# Low_Distortion_Oscillator_DCDC.net
KiCad netlist of a schematic drawn in Altium Designer
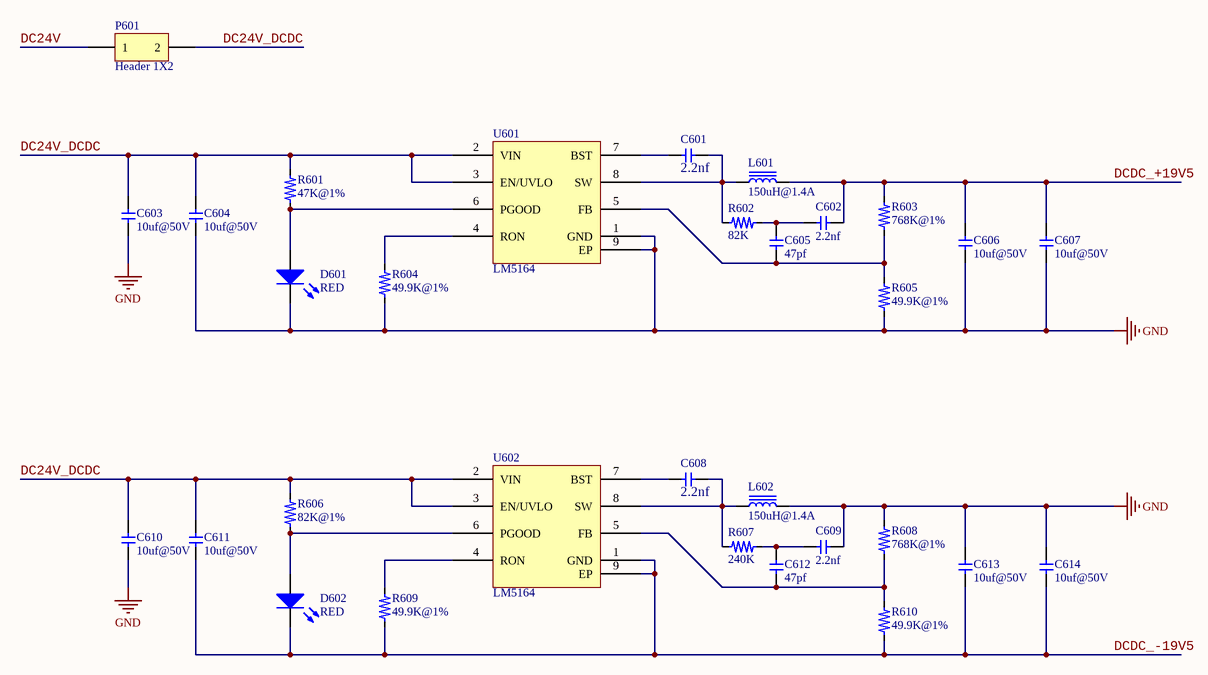
[diagram p0: Low Distortion Oscillator.DCDC.SchDoc]

(export (version "E")
  (design (tool "Eeschema 10.0.6"))
  (components
    (comp (ref "C601")
      (value "2.2nf")
      (footprint "C0603")
      (fields (field (name "Comment") "Cap"))
      (libsource (lib "carrot_lib") (part "Cap"))
    )
    (comp (ref "C602")
      (value "2.2nf")
      (footprint "C0603")
      (fields (field (name "Comment") "Cap"))
      (libsource (lib "carrot_lib") (part "Cap"))
    )
    (comp (ref "C603")
      (value "10uf@50V")
      (footprint "C1206")
      (fields (field (name "Comment") "Cap"))
      (libsource (lib "carrot_lib") (part "Cap"))
    )
    (comp (ref "C604")
      (value "10uf@50V")
      (footprint "C1206")
      (fields (field (name "Comment") "Cap"))
      (libsource (lib "carrot_lib") (part "Cap"))
    )
    (comp (ref "C605")
      (value "47pf")
      (footprint "C0603")
      (fields (field (name "Comment") "Cap"))
      (libsource (lib "carrot_lib") (part "Cap"))
    )
    (comp (ref "C606")
      (value "10uf@50V")
      (footprint "C1206")
      (fields (field (name "Comment") "Cap"))
      (libsource (lib "carrot_lib") (part "Cap"))
    )
    (comp (ref "C607")
      (value "10uf@50V")
      (footprint "C1206")
      (fields (field (name "Comment") "Cap"))
      (libsource (lib "carrot_lib") (part "Cap"))
    )
    (comp (ref "C608")
      (value "2.2nf")
      (footprint "C0603")
      (fields (field (name "Comment") "Cap"))
      (libsource (lib "carrot_lib") (part "Cap"))
    )
    (comp (ref "C609")
      (value "2.2nf")
      (footprint "C0603")
      (fields (field (name "Comment") "Cap"))
      (libsource (lib "carrot_lib") (part "Cap"))
    )
    (comp (ref "C610")
      (value "10uf@50V")
      (footprint "C1206")
      (fields (field (name "Comment") "Cap"))
      (libsource (lib "carrot_lib") (part "Cap"))
    )
    (comp (ref "C611")
      (value "10uf@50V")
      (footprint "C1206")
      (fields (field (name "Comment") "Cap"))
      (libsource (lib "carrot_lib") (part "Cap"))
    )
    (comp (ref "C612")
      (value "47pf")
      (footprint "C0603")
      (fields (field (name "Comment") "Cap"))
      (libsource (lib "carrot_lib") (part "Cap"))
    )
    (comp (ref "C613")
      (value "10uf@50V")
      (footprint "C1206")
      (fields (field (name "Comment") "Cap"))
      (libsource (lib "carrot_lib") (part "Cap"))
    )
    (comp (ref "C614")
      (value "10uf@50V")
      (footprint "C1206")
      (fields (field (name "Comment") "Cap"))
      (libsource (lib "carrot_lib") (part "Cap"))
    )
    (comp (ref "D601")
      (value "RED")
      (footprint "LED0603")
      (fields (field (name "Comment") "LED"))
      (libsource (lib "carrot_lib") (part "LED"))
    )
    (comp (ref "D602")
      (value "RED")
      (footprint "LED0603")
      (fields (field (name "Comment") "LED"))
      (libsource (lib "carrot_lib") (part "LED"))
    )
    (comp (ref "L601")
      (value "150uH@1.4A")
      (footprint "L12127")
      (description "Magnetic-Core Inductor")
      (fields (field (name "Comment") "Inductor Iron"))
      (libsource (lib "carrot_lib") (part "Inductor Iron"))
    )
    (comp (ref "L602")
      (value "150uH@1.4A")
      (footprint "L12127")
      (description "Magnetic-Core Inductor")
      (fields (field (name "Comment") "Inductor Iron"))
      (libsource (lib "carrot_lib") (part "Inductor Iron"))
    )
    (comp (ref "P601")
      (value "Header 1X2")
      (footprint "HDR2X1")
      (description "Header, 1-Pin, Dual row")
      (libsource (lib "carrot_lib") (part "Header 1X2"))
    )
    (comp (ref "R601")
      (value "47K@1%")
      (footprint "R0603")
      (description "电阻")
      (fields (field (name "Comment") "Res"))
      (libsource (lib "carrot_lib") (part "Res"))
    )
    (comp (ref "R602")
      (value "82K")
      (footprint "R0603")
      (description "电阻")
      (fields (field (name "Comment") "Res"))
      (libsource (lib "carrot_lib") (part "Res"))
    )
    (comp (ref "R603")
      (value "768K@1%")
      (footprint "R0603")
      (description "电阻")
      (fields (field (name "Comment") "Res"))
      (libsource (lib "carrot_lib") (part "Res"))
    )
    (comp (ref "R604")
      (value "49.9K@1%")
      (footprint "R0603")
      (description "电阻")
      (fields (field (name "Comment") "Res"))
      (libsource (lib "carrot_lib") (part "Res"))
    )
    (comp (ref "R605")
      (value "49.9K@1%")
      (footprint "R0603")
      (description "电阻")
      (fields (field (name "Comment") "Res"))
      (libsource (lib "carrot_lib") (part "Res"))
    )
    (comp (ref "R606")
      (value "82K@1%")
      (footprint "R0603")
      (description "电阻")
      (fields (field (name "Comment") "Res"))
      (libsource (lib "carrot_lib") (part "Res"))
    )
    (comp (ref "R607")
      (value "240K")
      (footprint "R0603")
      (description "电阻")
      (fields (field (name "Comment") "Res"))
      (libsource (lib "carrot_lib") (part "Res"))
    )
    (comp (ref "R608")
      (value "768K@1%")
      (footprint "R0603")
      (description "电阻")
      (fields (field (name "Comment") "Res"))
      (libsource (lib "carrot_lib") (part "Res"))
    )
    (comp (ref "R609")
      (value "49.9K@1%")
      (footprint "R0603")
      (description "电阻")
      (fields (field (name "Comment") "Res"))
      (libsource (lib "carrot_lib") (part "Res"))
    )
    (comp (ref "R610")
      (value "49.9K@1%")
      (footprint "R0603")
      (description "电阻")
      (fields (field (name "Comment") "Res"))
      (libsource (lib "carrot_lib") (part "Res"))
    )
    (comp (ref "U601")
      (value "LM5164")
      (footprint "LM5164-SOIC8")
      (description "LM5164 100-V Input, 1-A synchronous buck DC/DC converter with ultra-low IQ")
      (libsource (lib "carrot_lib") (part "LM5164"))
    )
    (comp (ref "U602")
      (value "LM5164")
      (footprint "LM5164-SOIC8")
      (description "LM5164 100-V Input, 1-A synchronous buck DC/DC converter with ultra-low IQ")
      (libsource (lib "carrot_lib") (part "LM5164"))
    )
  )
  (nets
    (net (code "1") (name "/DC24V") (class "Default")
      (node (ref "P601") (pin "1") (pinfunction "1_1") (pintype "passive"))
    )
    (net (code "2") (name "/DC24V_DCDC") (class "Default")
      (node (ref "C603") (pin "2") (pinfunction "2_2") (pintype "passive"))
      (node (ref "C604") (pin "2") (pinfunction "2_2") (pintype "passive"))
      (node (ref "C610") (pin "2") (pinfunction "2_2") (pintype "passive"))
      (node (ref "C611") (pin "2") (pinfunction "2_2") (pintype "passive"))
      (node (ref "P601") (pin "2") (pinfunction "2_2") (pintype "passive"))
      (node (ref "R601") (pin "2") (pinfunction "2_2") (pintype "passive"))
      (node (ref "R606") (pin "2") (pinfunction "2_2") (pintype "passive"))
      (node (ref "U601") (pin "2") (pinfunction "VIN_2") (pintype "passive"))
      (node (ref "U601") (pin "3") (pinfunction "EN/UVLO_3") (pintype "passive"))
      (node (ref "U602") (pin "2") (pinfunction "VIN_2") (pintype "passive"))
      (node (ref "U602") (pin "3") (pinfunction "EN/UVLO_3") (pintype "passive"))
    )
    (net (code "3") (name "/DCDC_+19V5") (class "Default")
      (node (ref "C602") (pin "2") (pinfunction "2_2") (pintype "passive"))
      (node (ref "C606") (pin "2") (pinfunction "2_2") (pintype "passive"))
      (node (ref "C607") (pin "2") (pinfunction "2_2") (pintype "passive"))
      (node (ref "L601") (pin "2") (pinfunction "2_2") (pintype "passive"))
      (node (ref "R603") (pin "2") (pinfunction "2_2") (pintype "passive"))
    )
    (net (code "4") (name "/DCDC_-19V5") (class "Default")
      (node (ref "C611") (pin "1") (pinfunction "1_1") (pintype "passive"))
      (node (ref "C613") (pin "1") (pinfunction "1_1") (pintype "passive"))
      (node (ref "C614") (pin "1") (pinfunction "1_1") (pintype "passive"))
      (node (ref "D602") (pin "2") (pinfunction "K_2") (pintype "passive"))
      (node (ref "R609") (pin "1") (pinfunction "1_1") (pintype "passive"))
      (node (ref "R610") (pin "1") (pinfunction "1_1") (pintype "passive"))
      (node (ref "U602") (pin "1") (pinfunction "GND_1") (pintype "passive"))
      (node (ref "U602") (pin "9") (pinfunction "EP_9") (pintype "passive"))
    )
    (net (code "5") (name "GND") (class "Default")
      (node (ref "C603") (pin "1") (pinfunction "1_1") (pintype "passive"))
      (node (ref "C604") (pin "1") (pinfunction "1_1") (pintype "passive"))
      (node (ref "C606") (pin "1") (pinfunction "1_1") (pintype "passive"))
      (node (ref "C607") (pin "1") (pinfunction "1_1") (pintype "passive"))
      (node (ref "C609") (pin "2") (pinfunction "2_2") (pintype "passive"))
      (node (ref "C610") (pin "1") (pinfunction "1_1") (pintype "passive"))
      (node (ref "C613") (pin "2") (pinfunction "2_2") (pintype "passive"))
      (node (ref "C614") (pin "2") (pinfunction "2_2") (pintype "passive"))
      (node (ref "D601") (pin "2") (pinfunction "K_2") (pintype "passive"))
      (node (ref "L602") (pin "2") (pinfunction "2_2") (pintype "passive"))
      (node (ref "R604") (pin "1") (pinfunction "1_1") (pintype "passive"))
      (node (ref "R605") (pin "1") (pinfunction "1_1") (pintype "passive"))
      (node (ref "R608") (pin "2") (pinfunction "2_2") (pintype "passive"))
      (node (ref "U601") (pin "1") (pinfunction "GND_1") (pintype "passive"))
      (node (ref "U601") (pin "9") (pinfunction "EP_9") (pintype "passive"))
    )
    (net (code "6") (name "Net-(C602-Pad1)") (class "Default")
      (node (ref "C602") (pin "1") (pinfunction "1_1") (pintype "passive"))
      (node (ref "C605") (pin "1") (pinfunction "1_1") (pintype "passive"))
      (node (ref "R602") (pin "1") (pinfunction "1_1") (pintype "passive"))
    )
    (net (code "7") (name "Net-(C609-Pad1)") (class "Default")
      (node (ref "C609") (pin "1") (pinfunction "1_1") (pintype "passive"))
      (node (ref "C612") (pin "1") (pinfunction "1_1") (pintype "passive"))
      (node (ref "R607") (pin "1") (pinfunction "1_1") (pintype "passive"))
    )
    (net (code "8") (name "Net-(D601-A)") (class "Default")
      (node (ref "D601") (pin "1") (pinfunction "A_1") (pintype "passive"))
      (node (ref "R601") (pin "1") (pinfunction "1_1") (pintype "passive"))
      (node (ref "U601") (pin "6") (pinfunction "PGOOD_6") (pintype "passive"))
    )
    (net (code "9") (name "Net-(D602-A)") (class "Default")
      (node (ref "D602") (pin "1") (pinfunction "A_1") (pintype "passive"))
      (node (ref "R606") (pin "1") (pinfunction "1_1") (pintype "passive"))
      (node (ref "U602") (pin "6") (pinfunction "PGOOD_6") (pintype "passive"))
    )
    (net (code "10") (name "Net-(U601-BST)") (class "Default")
      (node (ref "C601") (pin "2") (pinfunction "2_2") (pintype "passive"))
      (node (ref "U601") (pin "7") (pinfunction "BST_7") (pintype "passive"))
    )
    (net (code "11") (name "Net-(U601-FB)") (class "Default")
      (node (ref "C605") (pin "2") (pinfunction "2_2") (pintype "passive"))
      (node (ref "R603") (pin "1") (pinfunction "1_1") (pintype "passive"))
      (node (ref "R605") (pin "2") (pinfunction "2_2") (pintype "passive"))
      (node (ref "U601") (pin "5") (pinfunction "FB_5") (pintype "passive"))
    )
    (net (code "12") (name "Net-(U601-RON)") (class "Default")
      (node (ref "R604") (pin "2") (pinfunction "2_2") (pintype "passive"))
      (node (ref "U601") (pin "4") (pinfunction "RON_4") (pintype "passive"))
    )
    (net (code "13") (name "Net-(U601-SW)") (class "Default")
      (node (ref "C601") (pin "1") (pinfunction "1_1") (pintype "passive"))
      (node (ref "L601") (pin "1") (pinfunction "1_1") (pintype "passive"))
      (node (ref "R602") (pin "2") (pinfunction "2_2") (pintype "passive"))
      (node (ref "U601") (pin "8") (pinfunction "SW_8") (pintype "passive"))
    )
    (net (code "14") (name "Net-(U602-BST)") (class "Default")
      (node (ref "C608") (pin "2") (pinfunction "2_2") (pintype "passive"))
      (node (ref "U602") (pin "7") (pinfunction "BST_7") (pintype "passive"))
    )
    (net (code "15") (name "Net-(U602-FB)") (class "Default")
      (node (ref "C612") (pin "2") (pinfunction "2_2") (pintype "passive"))
      (node (ref "R608") (pin "1") (pinfunction "1_1") (pintype "passive"))
      (node (ref "R610") (pin "2") (pinfunction "2_2") (pintype "passive"))
      (node (ref "U602") (pin "5") (pinfunction "FB_5") (pintype "passive"))
    )
    (net (code "16") (name "Net-(U602-RON)") (class "Default")
      (node (ref "R609") (pin "2") (pinfunction "2_2") (pintype "passive"))
      (node (ref "U602") (pin "4") (pinfunction "RON_4") (pintype "passive"))
    )
    (net (code "17") (name "Net-(U602-SW)") (class "Default")
      (node (ref "C608") (pin "1") (pinfunction "1_1") (pintype "passive"))
      (node (ref "L602") (pin "1") (pinfunction "1_1") (pintype "passive"))
      (node (ref "R607") (pin "2") (pinfunction "2_2") (pintype "passive"))
      (node (ref "U602") (pin "8") (pinfunction "SW_8") (pintype "passive"))
    )
  )
)
